# PLD_Connectors.net
KiCad netlist of a schematic drawn in Altium Designer
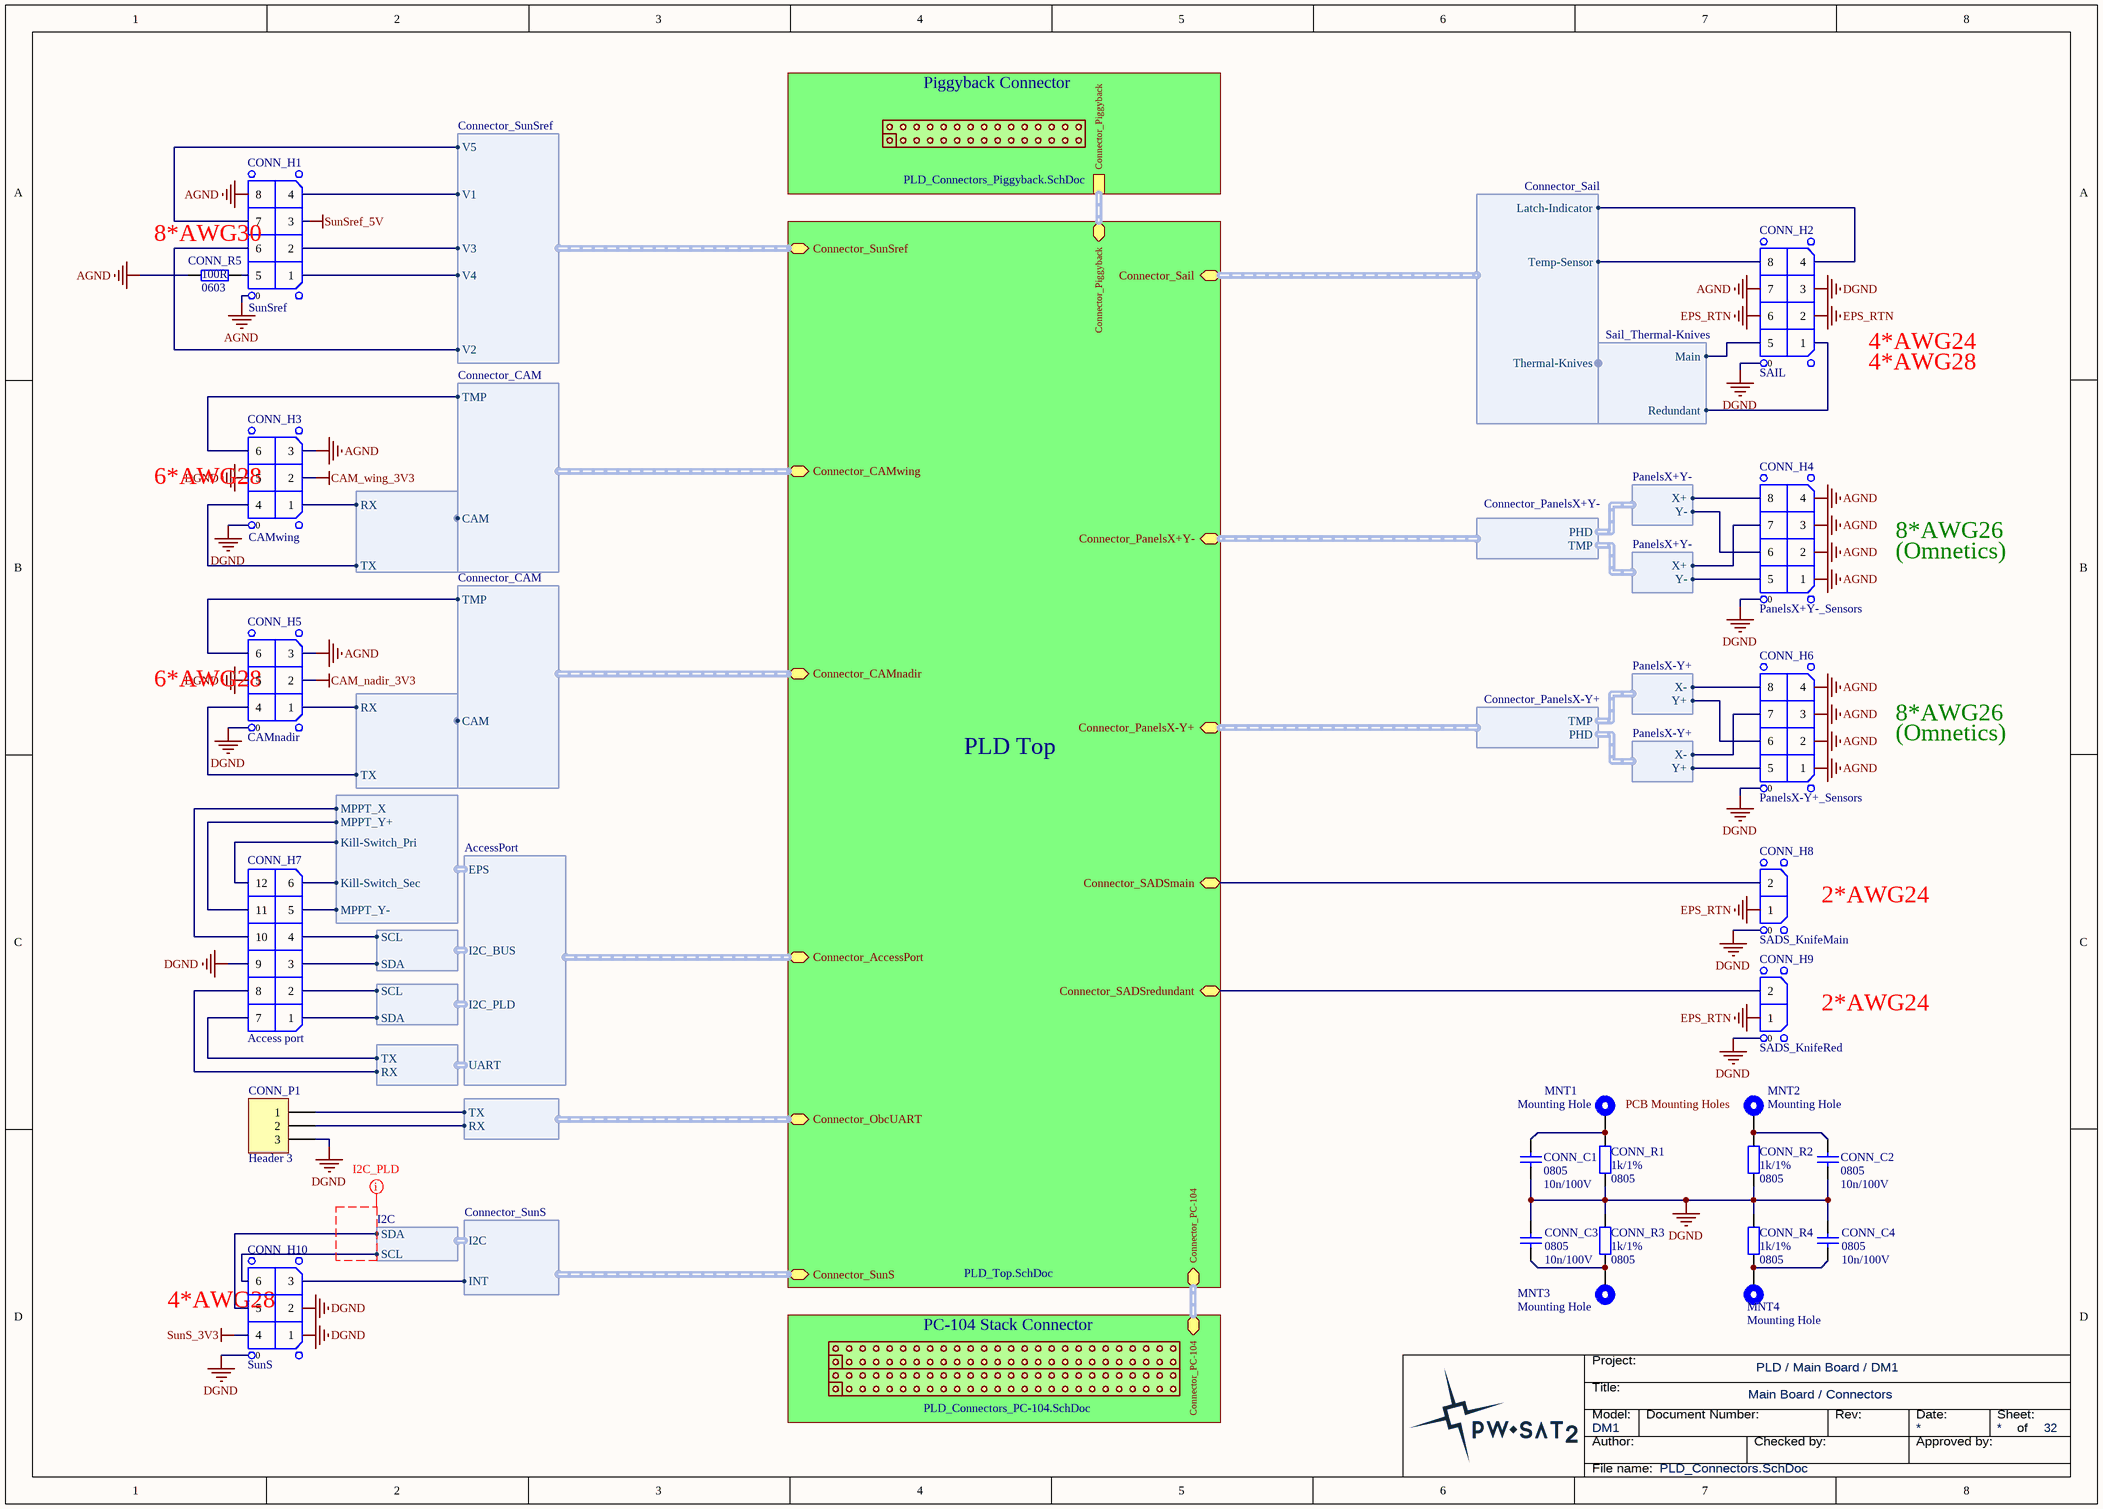
[diagram p0: PLD_Connectors.SchDoc]

(export (version "E")
  (design (tool "Eeschema 10.0.6"))
  (components
    (comp (ref "CONN_C1")
      (value "10n/100V")
      (footprint "SMD_Capacitor_0805")
      (description "Ceramic Cap Kemet COTS 100n/100V X7R 0805")
      (fields
        (field (name "MANUFACTURERPARTNUMBER") "C0805T104K1RCLTU")
        (field (name "MANUFACTURER") "Kemet")
        (field (name "PACKAGE") "0805")
      )
      (libsource (lib "capacitors") (part "Cer_C0805T104K1RCLTU"))
    )
    (comp (ref "CONN_C2")
      (value "10n/100V")
      (footprint "SMD_Capacitor_0805")
      (description "Ceramic Cap Kemet COTS 100n/100V X7R 0805")
      (fields
        (field (name "MANUFACTURERPARTNUMBER") "C0805T104K1RCLTU")
        (field (name "MANUFACTURER") "Kemet")
        (field (name "PACKAGE") "0805")
      )
      (libsource (lib "capacitors") (part "Cer_C0805T104K1RCLTU"))
    )
    (comp (ref "CONN_C3")
      (value "10n/100V")
      (footprint "SMD_Capacitor_0805")
      (description "Ceramic Cap Kemet COTS 100n/100V X7R 0805")
      (fields
        (field (name "MANUFACTURERPARTNUMBER") "C0805T104K1RCLTU")
        (field (name "MANUFACTURER") "Kemet")
        (field (name "PACKAGE") "0805")
      )
      (libsource (lib "capacitors") (part "Cer_C0805T104K1RCLTU"))
    )
    (comp (ref "CONN_C4")
      (value "10n/100V")
      (footprint "SMD_Capacitor_0805")
      (description "Ceramic Cap Kemet COTS 100n/100V X7R 0805")
      (fields
        (field (name "MANUFACTURERPARTNUMBER") "C0805T104K1RCLTU")
        (field (name "MANUFACTURER") "Kemet")
        (field (name "PACKAGE") "0805")
      )
      (libsource (lib "capacitors") (part "Cer_C0805T104K1RCLTU"))
    )
    (comp (ref "CONN_H1")
      (value "SunSref")
      (footprint "Harwin_Datamate_L-Tek_M80-8670805")
      (description "Harwin DataMate L-Tek, 2mm pitch, 2x4pin.")
      (libsource (lib "connectors_printed-circuit-board") (part "Harwin_Datamate_L-Tek_2x4pin"))
    )
    (comp (ref "CONN_H2")
      (value "SAIL")
      (footprint "Harwin_Datamate_L-Tek_M80-8670805")
      (description "Harwin DataMate L-Tek, 2mm pitch, 2x4pin.")
      (libsource (lib "connectors_printed-circuit-board") (part "Harwin_Datamate_L-Tek_2x4pin"))
    )
    (comp (ref "CONN_H3")
      (value "CAMwing")
      (footprint "Harwin_Datamate_L-Tek_M80-8670605")
      (description "Harwin DataMate L-Tek, 2mm pitch, 2x3pin.")
      (libsource (lib "connectors_printed-circuit-board") (part "Harwin_Datamate_L-Tek_2x3pin"))
    )
    (comp (ref "CONN_H4")
      (value "PanelsX+Y-_Sensors")
      (footprint "Harwin_Datamate_L-Tek_M80-8670805")
      (description "Harwin DataMate L-Tek, 2mm pitch, 2x4pin.")
      (libsource (lib "connectors_printed-circuit-board") (part "Harwin_Datamate_L-Tek_2x4pin"))
    )
    (comp (ref "CONN_H5")
      (value "CAMnadir")
      (footprint "Harwin_Datamate_L-Tek_M80-8670605")
      (description "Harwin DataMate L-Tek, 2mm pitch, 2x3pin.")
      (libsource (lib "connectors_printed-circuit-board") (part "Harwin_Datamate_L-Tek_2x3pin"))
    )
    (comp (ref "CONN_H6")
      (value "PanelsX-Y+_Sensors")
      (footprint "Harwin_Datamate_L-Tek_M80-8670805")
      (description "Harwin DataMate L-Tek, 2mm pitch, 2x4pin.")
      (libsource (lib "connectors_printed-circuit-board") (part "Harwin_Datamate_L-Tek_2x4pin"))
    )
    (comp (ref "CONN_H7")
      (value "Access port")
      (footprint "Harwin_Datamate_L-Tek_M80-8411242_W/O_RETAINING_STRAP")
      (description "Harwin DataMate L-Tek, 2mm pitch, 2x6pin.")
      (libsource (lib "connectors_printed-circuit-board") (part "Harwin_Datamate_L-Tek_2x6pin_W/O_RETAINING_STRAP"))
    )
    (comp (ref "CONN_H8")
      (value "SADS_KnifeMain")
      (footprint "Harwin_Datamate_L-Tek_M80-8770222")
      (description "Harwin DataMate L-Tek, 2mm pitch, 1x2pin.")
      (libsource (lib "connectors_printed-circuit-board") (part "Harwin_Datamate_L-Tek_1x2pin"))
    )
    (comp (ref "CONN_H9")
      (value "SADS_KnifeRed")
      (footprint "Harwin_Datamate_L-Tek_M80-8770222")
      (description "Harwin DataMate L-Tek, 2mm pitch, 1x2pin.")
      (libsource (lib "connectors_printed-circuit-board") (part "Harwin_Datamate_L-Tek_1x2pin"))
    )
    (comp (ref "CONN_H10")
      (value "SunS")
      (footprint "Harwin_Datamate_L-Tek_M80-8670605")
      (description "Harwin DataMate L-Tek, 2mm pitch, 2x3pin.")
      (libsource (lib "connectors_printed-circuit-board") (part "Harwin_Datamate_L-Tek_2x3pin"))
    )
    (comp (ref "CONN_P1")
      (value "Header 3")
      (footprint "HEADER 1X3 FEMALE")
      (description "Header, 3-Pin")
      (fields (field (name "PUBLISHER") "Altium Limited"))
      (libsource (lib "connectors_printed-circuit-board") (part "Header 3"))
    )
    (comp (ref "CONN_R1")
      (value "1k/1%")
      (footprint "SMD_Resistor_0805")
      (description "1k/1% Vishay CRCW 0805 Resistor. 125mW, 100ppm, 150V.")
      (fields
        (field (name "MANUFACTURER") "Vishay")
        (field (name "MANUFACTURERPARTNUMBER") "CRCW08051K00FKxxxx")
        (field (name "PACKAGE") "0805")
      )
      (libsource (lib "") (part "CRCW08051K00FKxxxx_1"))
    )
    (comp (ref "CONN_R2")
      (value "1k/1%")
      (footprint "SMD_Resistor_0805")
      (description "1k/1% Vishay CRCW 0805 Resistor. 125mW, 100ppm, 150V.")
      (fields
        (field (name "MANUFACTURER") "Vishay")
        (field (name "MANUFACTURERPARTNUMBER") "CRCW08051K00FKxxxx")
        (field (name "PACKAGE") "0805")
      )
      (libsource (lib "resistors") (part "CRCW08051K00FKxxxx"))
    )
    (comp (ref "CONN_R3")
      (value "1k/1%")
      (footprint "SMD_Resistor_0805")
      (description "1k/1% Vishay CRCW 0805 Resistor. 125mW, 100ppm, 150V.")
      (fields
        (field (name "MANUFACTURER") "Vishay")
        (field (name "MANUFACTURERPARTNUMBER") "CRCW08051K00FKxxxx")
        (field (name "PACKAGE") "0805")
      )
      (libsource (lib "") (part "CRCW08051K00FKxxxx_1"))
    )
    (comp (ref "CONN_R4")
      (value "1k/1%")
      (footprint "SMD_Resistor_0805")
      (description "1k/1% Vishay CRCW 0805 Resistor. 125mW, 100ppm, 150V.")
      (fields
        (field (name "MANUFACTURER") "Vishay")
        (field (name "MANUFACTURERPARTNUMBER") "CRCW08051K00FKxxxx")
        (field (name "PACKAGE") "0805")
      )
      (libsource (lib "resistors") (part "CRCW08051K00FKxxxx"))
    )
    (comp (ref "CONN_R5")
      (value "100R")
      (footprint "SMD_Resistor_0603")
      (fields (field (name "PACKAGE") "0603"))
      (libsource (lib "resistors") (part "Res"))
    )
    (comp (ref "MNT1")
      (value "Mounting Hole")
      (footprint "PC-104_PcbMntHole_M3")
      (description "PCB Mounting Hole")
      (libsource (lib "connectors_printed-circuit-board") (part "MntHole"))
    )
    (comp (ref "MNT2")
      (value "Mounting Hole")
      (footprint "PC-104_PcbMntHole_M3")
      (description "PCB Mounting Hole")
      (libsource (lib "connectors_printed-circuit-board") (part "MntHole"))
    )
    (comp (ref "MNT3")
      (value "Mounting Hole")
      (footprint "PC-104_PcbMntHole_M3")
      (description "PCB Mounting Hole")
      (libsource (lib "connectors_printed-circuit-board") (part "MntHole"))
    )
    (comp (ref "MNT4")
      (value "Mounting Hole")
      (footprint "PC-104_PcbMntHole_M3")
      (description "PCB Mounting Hole")
      (libsource (lib "connectors_printed-circuit-board") (part "MntHole"))
    )
  )
  (nets
    (net (code "15") (name "/Connector_SADSmain") (class "Default")
      (node (ref "CONN_H8") (pin "2") (pinfunction "2_2") (pintype "passive"))
    )
    (net (code "16") (name "/Connector_SADSredundant") (class "Default")
      (node (ref "CONN_H9") (pin "2") (pinfunction "2_2") (pintype "passive"))
    )
    (net (code "17") (name "/INT") (class "Default")
      (node (ref "CONN_H10") (pin "3") (pinfunction "3_3") (pintype "passive"))
    )
    (net (code "18") (name "/Kill-Switch_Pri") (class "Default")
      (node (ref "CONN_H7") (pin "12") (pinfunction "12_12") (pintype "passive"))
    )
    (net (code "19") (name "/Kill-Switch_Sec") (class "Default")
      (node (ref "CONN_H7") (pin "6") (pinfunction "6_6") (pintype "passive"))
    )
    (net (code "20") (name "/Latch-Indicator") (class "Default")
      (node (ref "CONN_H2") (pin "4") (pinfunction "4_4") (pintype "passive"))
    )
    (net (code "21") (name "/MPPT_X") (class "Default")
      (node (ref "CONN_H7") (pin "10") (pinfunction "10_10") (pintype "passive"))
    )
    (net (code "22") (name "/MPPT_Y+") (class "Default")
      (node (ref "CONN_H7") (pin "11") (pinfunction "11_11") (pintype "passive"))
    )
    (net (code "23") (name "/MPPT_Y-") (class "Default")
      (node (ref "CONN_H7") (pin "5") (pinfunction "5_5") (pintype "passive"))
    )
    (net (code "24") (name "/Main") (class "Default")
      (node (ref "CONN_H2") (pin "5") (pinfunction "5_5") (pintype "passive"))
    )
    (net (code "25") (name "/Redundant") (class "Default")
      (node (ref "CONN_H2") (pin "1") (pinfunction "1_1") (pintype "passive"))
    )
    (net (code "26") (name "/Temp-Sensor") (class "Default")
      (node (ref "CONN_H2") (pin "8") (pinfunction "8_8") (pintype "passive"))
    )
    (net (code "27") (name "/V1") (class "Default")
      (node (ref "CONN_H1") (pin "4") (pinfunction "4_4") (pintype "passive"))
    )
    (net (code "28") (name "/V2") (class "Default")
      (node (ref "CONN_H1") (pin "6") (pinfunction "6_6") (pintype "passive"))
    )
    (net (code "29") (name "/V3") (class "Default")
      (node (ref "CONN_H1") (pin "2") (pinfunction "2_2") (pintype "passive"))
    )
    (net (code "30") (name "/V4") (class "Default")
      (node (ref "CONN_H1") (pin "1") (pinfunction "1_1") (pintype "passive"))
    )
    (net (code "31") (name "/V5") (class "Default")
      (node (ref "CONN_H1") (pin "7") (pinfunction "7_7") (pintype "passive"))
    )
    (net (code "44") (name "AGND") (class "Default")
      (node (ref "CONN_H1") (pin "0") (pinfunction "0_0") (pintype "passive"))
      (node (ref "CONN_H1") (pin "8") (pinfunction "8_8") (pintype "passive"))
      (node (ref "CONN_H2") (pin "7") (pinfunction "7_7") (pintype "passive"))
      (node (ref "CONN_H3") (pin "3") (pinfunction "3_3") (pintype "passive"))
      (node (ref "CONN_H4") (pin "1") (pinfunction "1_1") (pintype "passive"))
      (node (ref "CONN_H4") (pin "2") (pinfunction "2_2") (pintype "passive"))
      (node (ref "CONN_H4") (pin "3") (pinfunction "3_3") (pintype "passive"))
      (node (ref "CONN_H4") (pin "4") (pinfunction "4_4") (pintype "passive"))
      (node (ref "CONN_H5") (pin "3") (pinfunction "3_3") (pintype "passive"))
      (node (ref "CONN_H6") (pin "1") (pinfunction "1_1") (pintype "passive"))
      (node (ref "CONN_H6") (pin "2") (pinfunction "2_2") (pintype "passive"))
      (node (ref "CONN_H6") (pin "3") (pinfunction "3_3") (pintype "passive"))
      (node (ref "CONN_H6") (pin "4") (pinfunction "4_4") (pintype "passive"))
      (node (ref "CONN_R5") (pin "1") (pinfunction "1_1") (pintype "passive"))
    )
    (net (code "45") (name "CAM_nadir_3V3") (class "Default")
      (node (ref "CONN_H5") (pin "2") (pinfunction "2_2") (pintype "passive"))
    )
    (net (code "46") (name "CAM_wing_3V3") (class "Default")
      (node (ref "CONN_H3") (pin "2") (pinfunction "2_2") (pintype "passive"))
    )
    (net (code "47") (name "DGND") (class "Default")
      (node (ref "CONN_C1") (pin "1") (pinfunction "1_1") (pintype "passive"))
      (node (ref "CONN_C2") (pin "1") (pinfunction "1_1") (pintype "passive"))
      (node (ref "CONN_C3") (pin "2") (pinfunction "2_2") (pintype "passive"))
      (node (ref "CONN_C4") (pin "2") (pinfunction "2_2") (pintype "passive"))
      (node (ref "CONN_H10") (pin "0") (pinfunction "0_0") (pintype "passive"))
      (node (ref "CONN_H10") (pin "1") (pinfunction "1_1") (pintype "passive"))
      (node (ref "CONN_H10") (pin "2") (pinfunction "2_2") (pintype "passive"))
      (node (ref "CONN_H2") (pin "0") (pinfunction "0_0") (pintype "passive"))
      (node (ref "CONN_H2") (pin "3") (pinfunction "3_3") (pintype "passive"))
      (node (ref "CONN_H3") (pin "0") (pinfunction "0_0") (pintype "passive"))
      (node (ref "CONN_H3") (pin "5") (pinfunction "5_5") (pintype "passive"))
      (node (ref "CONN_H4") (pin "0") (pinfunction "0_0") (pintype "passive"))
      (node (ref "CONN_H5") (pin "0") (pinfunction "0_0") (pintype "passive"))
      (node (ref "CONN_H5") (pin "5") (pinfunction "5_5") (pintype "passive"))
      (node (ref "CONN_H6") (pin "0") (pinfunction "0_0") (pintype "passive"))
      (node (ref "CONN_H7") (pin "9") (pinfunction "9_9") (pintype "passive"))
      (node (ref "CONN_H8") (pin "0") (pinfunction "0_0") (pintype "passive"))
      (node (ref "CONN_H9") (pin "0") (pinfunction "0_0") (pintype "passive"))
      (node (ref "CONN_P1") (pin "3") (pinfunction "3_3") (pintype "passive"))
      (node (ref "CONN_R1") (pin "1") (pinfunction "1_1") (pintype "passive"))
      (node (ref "CONN_R2") (pin "1") (pinfunction "1_1") (pintype "passive"))
      (node (ref "CONN_R3") (pin "2") (pinfunction "2_2") (pintype "passive"))
      (node (ref "CONN_R4") (pin "2") (pinfunction "2_2") (pintype "passive"))
    )
    (net (code "48") (name "EPS_RTN") (class "Default")
      (node (ref "CONN_H2") (pin "2") (pinfunction "2_2") (pintype "passive"))
      (node (ref "CONN_H2") (pin "6") (pinfunction "6_6") (pintype "passive"))
      (node (ref "CONN_H8") (pin "1") (pinfunction "1_1") (pintype "passive"))
      (node (ref "CONN_H9") (pin "1") (pinfunction "1_1") (pintype "passive"))
    )
    (net (code "49") (name "Net-(CONN_C1-Pad2)") (class "Default")
      (node (ref "CONN_C1") (pin "2") (pinfunction "2_2") (pintype "passive"))
      (node (ref "CONN_R1") (pin "2") (pinfunction "2_2") (pintype "passive"))
      (node (ref "MNT1") (pin "1") (pinfunction "1_1") (pintype "passive"))
    )
    (net (code "50") (name "Net-(CONN_C2-Pad2)") (class "Default")
      (node (ref "CONN_C2") (pin "2") (pinfunction "2_2") (pintype "passive"))
      (node (ref "CONN_R2") (pin "2") (pinfunction "2_2") (pintype "passive"))
      (node (ref "MNT2") (pin "1") (pinfunction "1_1") (pintype "passive"))
    )
    (net (code "51") (name "Net-(CONN_C3-Pad1)") (class "Default")
      (node (ref "CONN_C3") (pin "1") (pinfunction "1_1") (pintype "passive"))
      (node (ref "CONN_R3") (pin "1") (pinfunction "1_1") (pintype "passive"))
      (node (ref "MNT3") (pin "1") (pinfunction "1_1") (pintype "passive"))
    )
    (net (code "52") (name "Net-(CONN_C4-Pad1)") (class "Default")
      (node (ref "CONN_C4") (pin "1") (pinfunction "1_1") (pintype "passive"))
      (node (ref "CONN_R4") (pin "1") (pinfunction "1_1") (pintype "passive"))
      (node (ref "MNT4") (pin "1") (pinfunction "1_1") (pintype "passive"))
    )
    (net (code "53") (name "Net-(CONN_H1-Pad5)") (class "Default")
      (node (ref "CONN_H1") (pin "5") (pinfunction "5_5") (pintype "passive"))
      (node (ref "CONN_R5") (pin "2") (pinfunction "2_2") (pintype "passive"))
    )
    (net (code "54") (name "SunS_3V3") (class "Default")
      (node (ref "CONN_H10") (pin "4") (pinfunction "4_4") (pintype "passive"))
    )
    (net (code "55") (name "SunSref_5V") (class "Default")
      (node (ref "CONN_H1") (pin "3") (pinfunction "3_3") (pintype "passive"))
    )
    (net (code "56") (name "unconnected-(CONN_H3-Pad1)") (class "Default")
      (node (ref "CONN_H3") (pin "1") (pinfunction "1_1") (pintype "passive"))
    )
    (net (code "57") (name "unconnected-(CONN_H3-Pad4)") (class "Default")
      (node (ref "CONN_H3") (pin "4") (pinfunction "4_4") (pintype "passive"))
    )
    (net (code "58") (name "unconnected-(CONN_H3-Pad6)") (class "Default")
      (node (ref "CONN_H3") (pin "6") (pinfunction "6_6") (pintype "passive"))
    )
    (net (code "59") (name "unconnected-(CONN_H4-Pad5)") (class "Default")
      (node (ref "CONN_H4") (pin "5") (pinfunction "5_5") (pintype "passive"))
    )
    (net (code "60") (name "unconnected-(CONN_H4-Pad6)") (class "Default")
      (node (ref "CONN_H4") (pin "6") (pinfunction "6_6") (pintype "passive"))
    )
    (net (code "61") (name "unconnected-(CONN_H4-Pad7)") (class "Default")
      (node (ref "CONN_H4") (pin "7") (pinfunction "7_7") (pintype "passive"))
    )
    (net (code "62") (name "unconnected-(CONN_H4-Pad8)") (class "Default")
      (node (ref "CONN_H4") (pin "8") (pinfunction "8_8") (pintype "passive"))
    )
    (net (code "63") (name "unconnected-(CONN_H5-Pad1)") (class "Default")
      (node (ref "CONN_H5") (pin "1") (pinfunction "1_1") (pintype "passive"))
    )
    (net (code "64") (name "unconnected-(CONN_H5-Pad4)") (class "Default")
      (node (ref "CONN_H5") (pin "4") (pinfunction "4_4") (pintype "passive"))
    )
    (net (code "65") (name "unconnected-(CONN_H5-Pad6)") (class "Default")
      (node (ref "CONN_H5") (pin "6") (pinfunction "6_6") (pintype "passive"))
    )
    (net (code "66") (name "unconnected-(CONN_H6-Pad5)") (class "Default")
      (node (ref "CONN_H6") (pin "5") (pinfunction "5_5") (pintype "passive"))
    )
    (net (code "67") (name "unconnected-(CONN_H6-Pad6)") (class "Default")
      (node (ref "CONN_H6") (pin "6") (pinfunction "6_6") (pintype "passive"))
    )
    (net (code "68") (name "unconnected-(CONN_H6-Pad7)") (class "Default")
      (node (ref "CONN_H6") (pin "7") (pinfunction "7_7") (pintype "passive"))
    )
    (net (code "69") (name "unconnected-(CONN_H6-Pad8)") (class "Default")
      (node (ref "CONN_H6") (pin "8") (pinfunction "8_8") (pintype "passive"))
    )
    (net (code "70") (name "unconnected-(CONN_H7-Pad1)") (class "Default")
      (node (ref "CONN_H7") (pin "1") (pinfunction "1_1") (pintype "passive"))
    )
    (net (code "71") (name "unconnected-(CONN_H7-Pad2)") (class "Default")
      (node (ref "CONN_H7") (pin "2") (pinfunction "2_2") (pintype "passive"))
    )
    (net (code "72") (name "unconnected-(CONN_H7-Pad3)") (class "Default")
      (node (ref "CONN_H7") (pin "3") (pinfunction "3_3") (pintype "passive"))
    )
    (net (code "73") (name "unconnected-(CONN_H7-Pad4)") (class "Default")
      (node (ref "CONN_H7") (pin "4") (pinfunction "4_4") (pintype "passive"))
    )
    (net (code "74") (name "unconnected-(CONN_H7-Pad7)") (class "Default")
      (node (ref "CONN_H7") (pin "7") (pinfunction "7_7") (pintype "passive"))
    )
    (net (code "75") (name "unconnected-(CONN_H7-Pad8)") (class "Default")
      (node (ref "CONN_H7") (pin "8") (pinfunction "8_8") (pintype "passive"))
    )
    (net (code "76") (name "unconnected-(CONN_H10-Pad5)") (class "Default")
      (node (ref "CONN_H10") (pin "5") (pinfunction "5_5") (pintype "passive"))
    )
    (net (code "77") (name "unconnected-(CONN_H10-Pad6)") (class "Default")
      (node (ref "CONN_H10") (pin "6") (pinfunction "6_6") (pintype "passive"))
    )
    (net (code "78") (name "unconnected-(CONN_P1-Pad1)") (class "Default")
      (node (ref "CONN_P1") (pin "1") (pinfunction "1_1") (pintype "passive"))
    )
    (net (code "79") (name "unconnected-(CONN_P1-Pad2)") (class "Default")
      (node (ref "CONN_P1") (pin "2") (pinfunction "2_2") (pintype "passive"))
    )
  )
)
